# ESP32_DevKit.net
KiCad netlist of a schematic drawn in Altium Designer
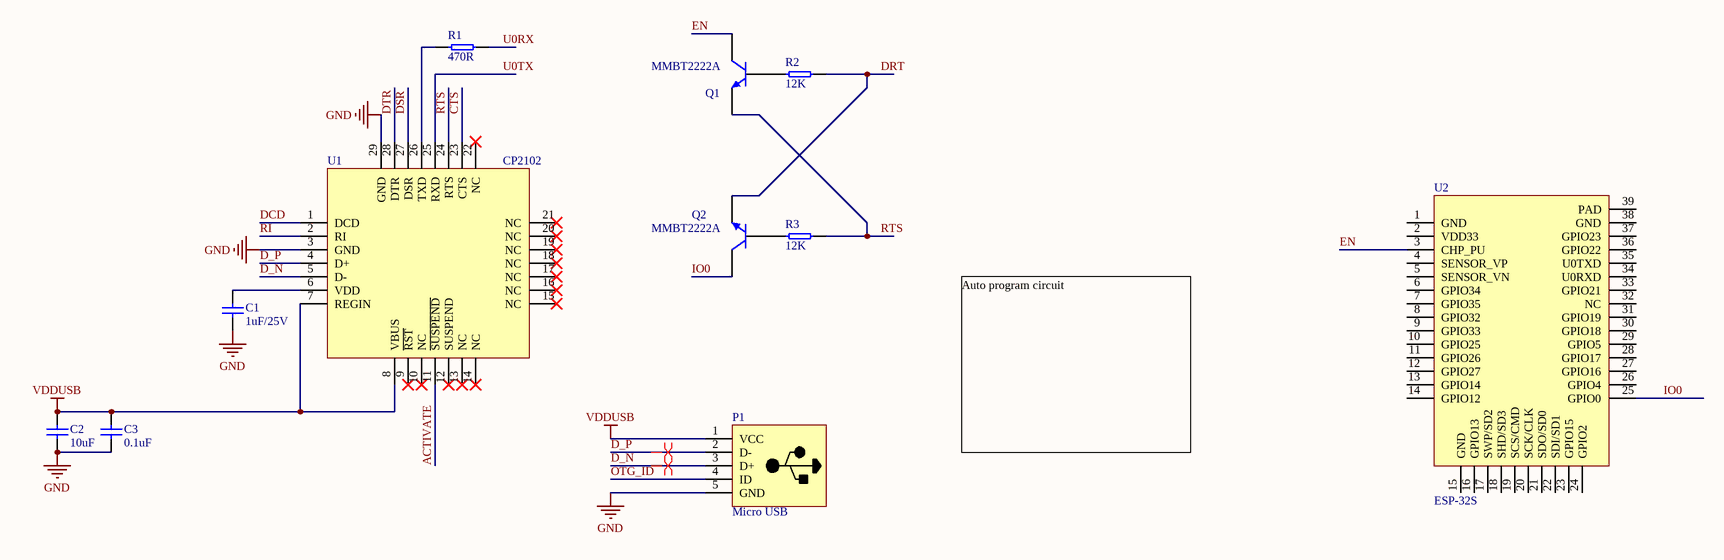
[diagram p0: ESP32_DevKit.SchDoc]

(export (version "E")
  (design (tool "Eeschema 10.0.6"))
  (components
    (comp (ref "C1")
      (value "1uF/25V")
      (footprint "C0805")
      (description "CAP CER 1UF 25V X7R 0805")
      (fields
        (field (name "MANUFACTURER") "TDK")
        (field (name "MANUFACTURER PART NUMBER") "CGA4J3X7R1E105K125AB")
      )
      (libsource (lib "ThangTM_Sch") (part "C1uF_0805"))
    )
    (comp (ref "C2")
      (value "10uF")
      (footprint "C0805")
      (description "CAP CER 10UF 6.3V X5R 0805")
      (fields
        (field (name "MANUFACTURER") "Samsung")
        (field (name "MANUFACTURER PART NUMBER") "CL21A106KQCLRNC")
      )
      (libsource (lib "ThangTM_Sch") (part "C10uF_0805"))
    )
    (comp (ref "C3") (value "0.1uF") (footprint "C0603") (libsource (lib "ThangTM_Sch") (part "C0.1uF_0603")))
    (comp (ref "P1") (value "Micro USB") (libsource (lib "ThangTM_Sch") (part "Micro_USB")))
    (comp (ref "Q1")
      (value "MMBT2222A")
      (footprint "SOT_23")
      (description "Transistors Bipolar - BJT SOT-23 NPN GEN PUR")
      (fields (field (name "BSH PART NUMBER") "Q-MMBT2222A"))
      (libsource (lib "ThangTM_Sch") (part "MMBT2222A"))
    )
    (comp (ref "Q2")
      (value "MMBT2222A")
      (footprint "SOT_23")
      (description "Transistors Bipolar - BJT SOT-23 NPN GEN PUR")
      (fields (field (name "BSH PART NUMBER") "Q-MMBT2222A"))
      (libsource (lib "ThangTM_Sch") (part "MMBT2222A"))
    )
    (comp (ref "R1") (value "470R") (footprint "R0805") (libsource (lib "ThangTM_Sch") (part "R470R_0805")))
    (comp (ref "R2")
      (value "12K")
      (footprint "R0805")
      (description "RES SMD 12K OHM 5% 1/8W 0805")
      (fields
        (field (name "MANUFACTURER") "Yageo")
        (field (name "MANUFACTURER PART NUMBER") "RC0805JR-0712KL")
      )
      (libsource (lib "ThangTM_Sch") (part "R12K_0805"))
    )
    (comp (ref "R3")
      (value "12K")
      (footprint "R0805")
      (description "RES SMD 12K OHM 5% 1/8W 0805")
      (fields
        (field (name "MANUFACTURER") "Yageo")
        (field (name "MANUFACTURER PART NUMBER") "RC0805JR-0712KL")
      )
      (libsource (lib "ThangTM_Sch") (part "R12K_0805"))
    )
    (comp (ref "U1") (value "CP2102") (libsource (lib "ThangTM_Sch") (part "CP2102")))
    (comp (ref "U2") (value "ESP-32S") (libsource (lib "ThangTM_Sch") (part "ESP-32S")))
  )
  (nets
    (net (code "1") (name "/ACTIVATE") (class "Default")
      (node (ref "U1") (pin "11") (pinfunction "~{SUSPEND}_11") (pintype "passive"))
    )
    (net (code "2") (name "/CTS") (class "Default")
      (node (ref "U1") (pin "23") (pinfunction "CTS_23") (pintype "passive"))
    )
    (net (code "3") (name "/DCD") (class "Default")
      (node (ref "U1") (pin "1") (pinfunction "DCD_1") (pintype "passive"))
    )
    (net (code "4") (name "/DRT") (class "Default")
      (node (ref "Q2") (pin "3") (pinfunction "E_3") (pintype "passive"))
      (node (ref "R2") (pin "2") (pinfunction "2_2") (pintype "passive"))
    )
    (net (code "5") (name "/DSR") (class "Default")
      (node (ref "U1") (pin "27") (pinfunction "DSR_27") (pintype "passive"))
    )
    (net (code "6") (name "/DTR") (class "Default")
      (node (ref "U1") (pin "28") (pinfunction "DTR_28") (pintype "passive"))
    )
    (net (code "7") (name "/D_N") (class "Default")
      (node (ref "P1") (pin "3") (pinfunction "D+_3") (pintype "passive"))
      (node (ref "U1") (pin "5") (pinfunction "D-_5") (pintype "passive"))
    )
    (net (code "8") (name "/D_P") (class "Default")
      (node (ref "P1") (pin "2") (pinfunction "D-_2") (pintype "passive"))
      (node (ref "U1") (pin "4") (pinfunction "D+_4") (pintype "passive"))
    )
    (net (code "9") (name "/EN") (class "Default")
      (node (ref "Q1") (pin "2") (pinfunction "C_2") (pintype "passive"))
      (node (ref "U2") (pin "3") (pinfunction "CHP_PU_3") (pintype "passive"))
    )
    (net (code "10") (name "/IO0") (class "Default")
      (node (ref "Q2") (pin "2") (pinfunction "C_2") (pintype "passive"))
      (node (ref "U2") (pin "25") (pinfunction "GPIO0_25") (pintype "passive"))
    )
    (net (code "11") (name "/OTG_ID") (class "Default")
      (node (ref "P1") (pin "4") (pinfunction "ID_4") (pintype "passive"))
    )
    (net (code "12") (name "/RI") (class "Default")
      (node (ref "U1") (pin "2") (pinfunction "RI_2") (pintype "passive"))
    )
    (net (code "13") (name "/RTS") (class "Default")
      (node (ref "Q1") (pin "3") (pinfunction "E_3") (pintype "passive"))
      (node (ref "R3") (pin "2") (pinfunction "2_2") (pintype "passive"))
      (node (ref "U1") (pin "24") (pinfunction "RTS_24") (pintype "passive"))
    )
    (net (code "14") (name "/U0RX") (class "Default")
      (node (ref "R1") (pin "1") (pinfunction "1_1") (pintype "passive"))
    )
    (net (code "15") (name "/U0TX") (class "Default")
      (node (ref "U1") (pin "25") (pinfunction "RXD_25") (pintype "passive"))
    )
    (net (code "16") (name "GND") (class "Default")
      (node (ref "C1") (pin "1") (pinfunction "1_1") (pintype "passive"))
      (node (ref "C2") (pin "1") (pinfunction "1_1") (pintype "passive"))
      (node (ref "C3") (pin "1") (pinfunction "1_1") (pintype "passive"))
      (node (ref "P1") (pin "5") (pinfunction "GND_5") (pintype "passive"))
      (node (ref "U1") (pin "29") (pinfunction "GND_29") (pintype "passive"))
      (node (ref "U1") (pin "3") (pinfunction "GND_3") (pintype "passive"))
    )
    (net (code "17") (name "Net-(Q1-B)") (class "Default")
      (node (ref "Q1") (pin "1") (pinfunction "B_1") (pintype "passive"))
      (node (ref "R2") (pin "1") (pinfunction "1_1") (pintype "passive"))
    )
    (net (code "18") (name "Net-(Q2-B)") (class "Default")
      (node (ref "Q2") (pin "1") (pinfunction "B_1") (pintype "passive"))
      (node (ref "R3") (pin "1") (pinfunction "1_1") (pintype "passive"))
    )
    (net (code "19") (name "Net-(U1-TXD)") (class "Default")
      (node (ref "R1") (pin "2") (pinfunction "2_2") (pintype "passive"))
      (node (ref "U1") (pin "26") (pinfunction "TXD_26") (pintype "passive"))
    )
    (net (code "20") (name "Net-(U1-VDD)") (class "Default")
      (node (ref "C1") (pin "2") (pinfunction "2_2") (pintype "passive"))
      (node (ref "U1") (pin "6") (pinfunction "VDD_6") (pintype "passive"))
    )
    (net (code "21") (name "VDDUSB") (class "Default")
      (node (ref "C2") (pin "2") (pinfunction "2_2") (pintype "passive"))
      (node (ref "C3") (pin "2") (pinfunction "2_2") (pintype "passive"))
      (node (ref "P1") (pin "1") (pinfunction "VCC_1") (pintype "passive"))
      (node (ref "U1") (pin "7") (pinfunction "REGIN_7") (pintype "passive"))
      (node (ref "U1") (pin "8") (pinfunction "VBUS_8") (pintype "passive"))
    )
    (net (code "22") (name "unconnected-(U1-NC-Pad10)") (class "Default")
      (node (ref "U1") (pin "10") (pinfunction "NC_10") (pintype "passive+no_connect"))
    )
    (net (code "23") (name "unconnected-(U1-NC-Pad13)") (class "Default")
      (node (ref "U1") (pin "13") (pinfunction "NC_13") (pintype "passive+no_connect"))
    )
    (net (code "24") (name "unconnected-(U1-NC-Pad14)") (class "Default")
      (node (ref "U1") (pin "14") (pinfunction "NC_14") (pintype "passive+no_connect"))
    )
    (net (code "25") (name "unconnected-(U1-NC-Pad15)") (class "Default")
      (node (ref "U1") (pin "15") (pinfunction "NC_15") (pintype "passive+no_connect"))
    )
    (net (code "26") (name "unconnected-(U1-NC-Pad16)") (class "Default")
      (node (ref "U1") (pin "16") (pinfunction "NC_16") (pintype "passive+no_connect"))
    )
    (net (code "27") (name "unconnected-(U1-NC-Pad17)") (class "Default")
      (node (ref "U1") (pin "17") (pinfunction "NC_17") (pintype "passive+no_connect"))
    )
    (net (code "28") (name "unconnected-(U1-NC-Pad18)") (class "Default")
      (node (ref "U1") (pin "18") (pinfunction "NC_18") (pintype "passive+no_connect"))
    )
    (net (code "29") (name "unconnected-(U1-NC-Pad19)") (class "Default")
      (node (ref "U1") (pin "19") (pinfunction "NC_19") (pintype "passive+no_connect"))
    )
    (net (code "30") (name "unconnected-(U1-NC-Pad20)") (class "Default")
      (node (ref "U1") (pin "20") (pinfunction "NC_20") (pintype "passive+no_connect"))
    )
    (net (code "31") (name "unconnected-(U1-NC-Pad21)") (class "Default")
      (node (ref "U1") (pin "21") (pinfunction "NC_21") (pintype "passive+no_connect"))
    )
    (net (code "32") (name "unconnected-(U1-NC-Pad22)") (class "Default")
      (node (ref "U1") (pin "22") (pinfunction "NC_22") (pintype "passive+no_connect"))
    )
    (net (code "33") (name "unconnected-(U1-SUSPEND-Pad12)") (class "Default")
      (node (ref "U1") (pin "12") (pinfunction "SUSPEND_12") (pintype "passive+no_connect"))
    )
    (net (code "34") (name "unconnected-(U1-~{RST}-Pad9)") (class "Default")
      (node (ref "U1") (pin "9") (pinfunction "~{RST}_9") (pintype "passive+no_connect"))
    )
    (net (code "35") (name "unconnected-(U2-GND-Pad1)") (class "Default")
      (node (ref "U2") (pin "1") (pinfunction "GND_1") (pintype "passive"))
    )
    (net (code "36") (name "unconnected-(U2-GND-Pad15)") (class "Default")
      (node (ref "U2") (pin "15") (pinfunction "GND_15") (pintype "passive"))
    )
    (net (code "37") (name "unconnected-(U2-GND-Pad38)") (class "Default")
      (node (ref "U2") (pin "38") (pinfunction "GND_38") (pintype "passive"))
    )
    (net (code "38") (name "unconnected-(U2-GPIO2-Pad24)") (class "Default")
      (node (ref "U2") (pin "24") (pinfunction "GPIO2_24") (pintype "passive"))
    )
    (net (code "39") (name "unconnected-(U2-GPIO4-Pad26)") (class "Default")
      (node (ref "U2") (pin "26") (pinfunction "GPIO4_26") (pintype "passive"))
    )
    (net (code "40") (name "unconnected-(U2-GPIO5-Pad29)") (class "Default")
      (node (ref "U2") (pin "29") (pinfunction "GPIO5_29") (pintype "passive"))
    )
    (net (code "41") (name "unconnected-(U2-GPIO12-Pad14)") (class "Default")
      (node (ref "U2") (pin "14") (pinfunction "GPIO12_14") (pintype "passive"))
    )
    (net (code "42") (name "unconnected-(U2-GPIO13-Pad16)") (class "Default")
      (node (ref "U2") (pin "16") (pinfunction "GPIO13_16") (pintype "passive"))
    )
    (net (code "43") (name "unconnected-(U2-GPIO14-Pad13)") (class "Default")
      (node (ref "U2") (pin "13") (pinfunction "GPIO14_13") (pintype "passive"))
    )
    (net (code "44") (name "unconnected-(U2-GPIO15-Pad23)") (class "Default")
      (node (ref "U2") (pin "23") (pinfunction "GPIO15_23") (pintype "passive"))
    )
    (net (code "45") (name "unconnected-(U2-GPIO16-Pad27)") (class "Default")
      (node (ref "U2") (pin "27") (pinfunction "GPIO16_27") (pintype "passive"))
    )
    (net (code "46") (name "unconnected-(U2-GPIO17-Pad28)") (class "Default")
      (node (ref "U2") (pin "28") (pinfunction "GPIO17_28") (pintype "passive"))
    )
    (net (code "47") (name "unconnected-(U2-GPIO18-Pad30)") (class "Default")
      (node (ref "U2") (pin "30") (pinfunction "GPIO18_30") (pintype "passive"))
    )
    (net (code "48") (name "unconnected-(U2-GPIO19-Pad31)") (class "Default")
      (node (ref "U2") (pin "31") (pinfunction "GPIO19_31") (pintype "passive"))
    )
    (net (code "49") (name "unconnected-(U2-GPIO21-Pad33)") (class "Default")
      (node (ref "U2") (pin "33") (pinfunction "GPIO21_33") (pintype "passive"))
    )
    (net (code "50") (name "unconnected-(U2-GPIO22-Pad36)") (class "Default")
      (node (ref "U2") (pin "36") (pinfunction "GPIO22_36") (pintype "passive"))
    )
    (net (code "51") (name "unconnected-(U2-GPIO23-Pad37)") (class "Default")
      (node (ref "U2") (pin "37") (pinfunction "GPIO23_37") (pintype "passive"))
    )
    (net (code "52") (name "unconnected-(U2-GPIO25-Pad10)") (class "Default")
      (node (ref "U2") (pin "10") (pinfunction "GPIO25_10") (pintype "passive"))
    )
    (net (code "53") (name "unconnected-(U2-GPIO26-Pad11)") (class "Default")
      (node (ref "U2") (pin "11") (pinfunction "GPIO26_11") (pintype "passive"))
    )
    (net (code "54") (name "unconnected-(U2-GPIO27-Pad12)") (class "Default")
      (node (ref "U2") (pin "12") (pinfunction "GPIO27_12") (pintype "passive"))
    )
    (net (code "55") (name "unconnected-(U2-GPIO32-Pad8)") (class "Default")
      (node (ref "U2") (pin "8") (pinfunction "GPIO32_8") (pintype "passive"))
    )
    (net (code "56") (name "unconnected-(U2-GPIO33-Pad9)") (class "Default")
      (node (ref "U2") (pin "9") (pinfunction "GPIO33_9") (pintype "passive"))
    )
    (net (code "57") (name "unconnected-(U2-GPIO34-Pad6)") (class "Default")
      (node (ref "U2") (pin "6") (pinfunction "GPIO34_6") (pintype "passive"))
    )
    (net (code "58") (name "unconnected-(U2-GPIO35-Pad7)") (class "Default")
      (node (ref "U2") (pin "7") (pinfunction "GPIO35_7") (pintype "passive"))
    )
    (net (code "59") (name "unconnected-(U2-NC-Pad32)") (class "Default")
      (node (ref "U2") (pin "32") (pinfunction "NC_32") (pintype "passive"))
    )
    (net (code "60") (name "unconnected-(U2-PAD-Pad39)") (class "Default")
      (node (ref "U2") (pin "39") (pinfunction "PAD_39") (pintype "passive"))
    )
    (net (code "61") (name "unconnected-(U2-SCK{slash}CLK-Pad20)") (class "Default")
      (node (ref "U2") (pin "20") (pinfunction "SCK/CLK_20") (pintype "passive"))
    )
    (net (code "62") (name "unconnected-(U2-SCS{slash}CMD-Pad19)") (class "Default")
      (node (ref "U2") (pin "19") (pinfunction "SCS/CMD_19") (pintype "passive"))
    )
    (net (code "63") (name "unconnected-(U2-SDI{slash}SD1-Pad22)") (class "Default")
      (node (ref "U2") (pin "22") (pinfunction "SDI/SD1_22") (pintype "passive"))
    )
    (net (code "64") (name "unconnected-(U2-SDO{slash}SD0-Pad21)") (class "Default")
      (node (ref "U2") (pin "21") (pinfunction "SDO/SD0_21") (pintype "passive"))
    )
    (net (code "65") (name "unconnected-(U2-SENSOR_VN-Pad5)") (class "Default")
      (node (ref "U2") (pin "5") (pinfunction "SENSOR_VN_5") (pintype "passive"))
    )
    (net (code "66") (name "unconnected-(U2-SENSOR_VP-Pad4)") (class "Default")
      (node (ref "U2") (pin "4") (pinfunction "SENSOR_VP_4") (pintype "passive"))
    )
    (net (code "67") (name "unconnected-(U2-SHD{slash}SD3-Pad18)") (class "Default")
      (node (ref "U2") (pin "18") (pinfunction "SHD/SD3_18") (pintype "passive"))
    )
    (net (code "68") (name "unconnected-(U2-SWP{slash}SD2-Pad17)") (class "Default")
      (node (ref "U2") (pin "17") (pinfunction "SWP/SD2_17") (pintype "passive"))
    )
    (net (code "69") (name "unconnected-(U2-U0RXD-Pad34)") (class "Default")
      (node (ref "U2") (pin "34") (pinfunction "U0RXD_34") (pintype "passive"))
    )
    (net (code "70") (name "unconnected-(U2-U0TXD-Pad35)") (class "Default")
      (node (ref "U2") (pin "35") (pinfunction "U0TXD_35") (pintype "passive"))
    )
    (net (code "71") (name "unconnected-(U2-VDD33-Pad2)") (class "Default")
      (node (ref "U2") (pin "2") (pinfunction "VDD33_2") (pintype "passive"))
    )
  )
)
